# Sparkfun_MPU-9150_breakout.net
KiCad netlist of a schematic drawn in EAGLE
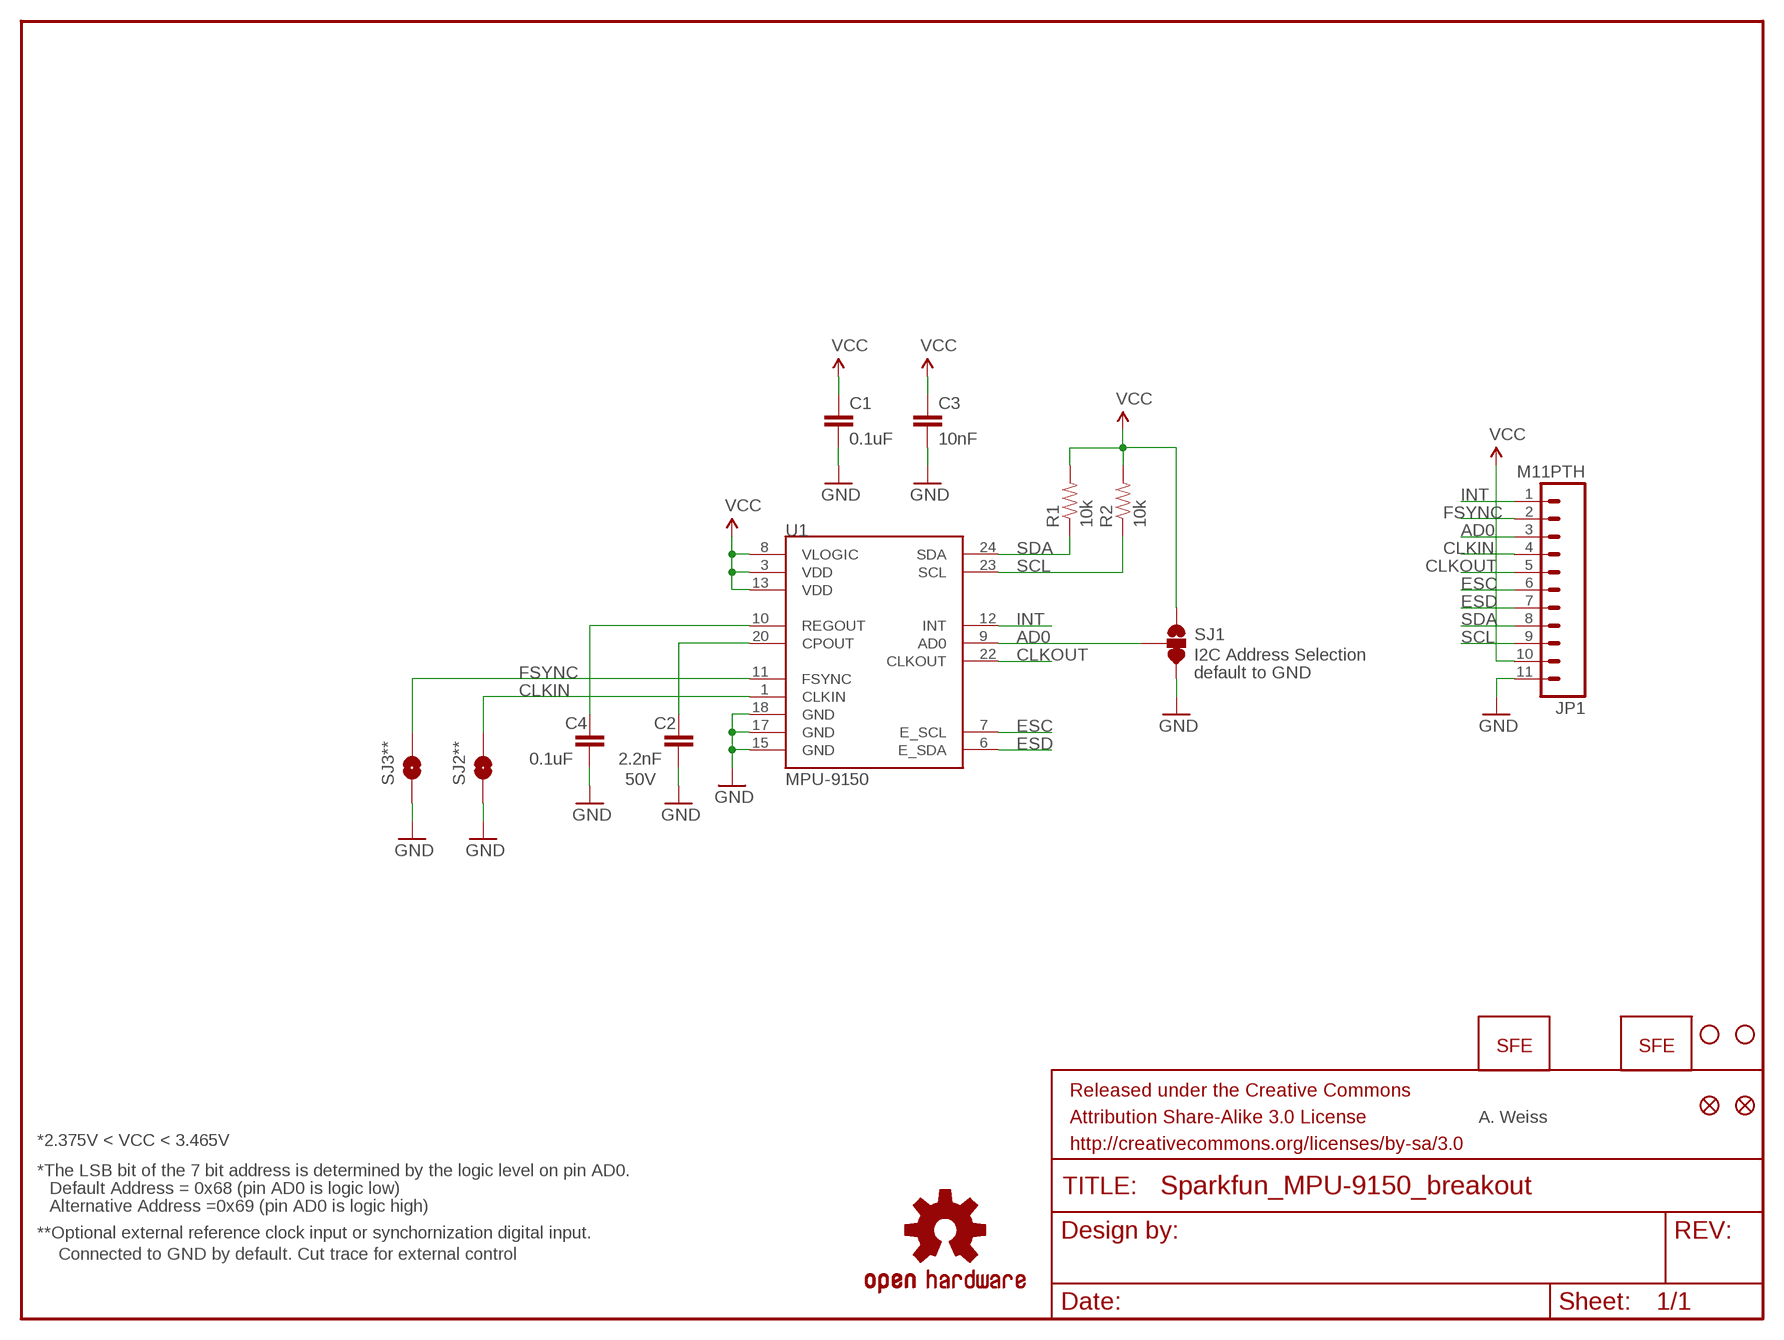
[diagram p0: schematic, sheet 1]

(export (version "E")
  (design (tool "Eeschema 10.0.6"))
  (components
    (comp (ref "C1")
      (value "0.1uF")
      (footprint "eagle-import:0402-CAP")
      (libsource (lib "eagle-import") (part "CAP0402-CAP"))
    )
    (comp (ref "C2")
      (value "2.2nF")
      (footprint "eagle-import:0402-CAP")
      (libsource (lib "eagle-import") (part "CAP0402-CAP"))
    )
    (comp (ref "C3")
      (value "10nF")
      (footprint "eagle-import:0402-CAP")
      (libsource (lib "eagle-import") (part "CAP0402-CAP"))
    )
    (comp (ref "C4")
      (value "0.1uF")
      (footprint "eagle-import:0402-CAP")
      (libsource (lib "eagle-import") (part "CAP0402-CAP"))
    )
    (comp (ref "JP1")
      (value "M11PTH")
      (footprint "eagle-import:1X11")
      (libsource (lib "eagle-import") (part "M11PTH"))
    )
    (comp (ref "JP2")
      (value "STAND-OFF")
      (footprint "eagle-import:STAND-OFF")
      (libsource (lib "eagle-import") (part "STAND-OFF"))
    )
    (comp (ref "JP3")
      (value "STAND-OFF")
      (footprint "eagle-import:STAND-OFF")
      (libsource (lib "eagle-import") (part "STAND-OFF"))
    )
    (comp (ref "JP4")
      (value "LOGO-SFENW2")
      (footprint "eagle-import:SFE-NEW-WEB")
      (libsource (lib "eagle-import") (part "LOGO-SFENW2"))
    )
    (comp (ref "JP6")
      (value "LOGO-SFESK")
      (footprint "eagle-import:SFE-LOGO-FLAME")
      (libsource (lib "eagle-import") (part "LOGO-SFESK"))
    )
    (comp (ref "JP7")
      (value "FIDUCIALUFIDUCIAL")
      (footprint "eagle-import:MICRO-FIDUCIAL")
      (libsource (lib "eagle-import") (part "FIDUCIALUFIDUCIAL"))
    )
    (comp (ref "JP8")
      (value "FIDUCIALUFIDUCIAL")
      (footprint "eagle-import:MICRO-FIDUCIAL")
      (libsource (lib "eagle-import") (part "FIDUCIALUFIDUCIAL"))
    )
    (comp (ref "R1")
      (value "10k")
      (footprint "eagle-import:0402-RES")
      (libsource (lib "eagle-import") (part "RESISTOR0402-RES"))
    )
    (comp (ref "R2")
      (value "10k")
      (footprint "eagle-import:0402-RES")
      (libsource (lib "eagle-import") (part "RESISTOR0402-RES"))
    )
    (comp (ref "SJ1")
      (value "SOLDERJUMPER_2WAYPASTE2&3")
      (footprint "eagle-import:SJ_3_PASTE2&3")
      (libsource (lib "eagle-import") (part "SOLDERJUMPER_2WAYPASTE2&3"))
    )
    (comp (ref "SJ2**")
      (value "SOLDERJUMPERTRACE")
      (footprint "eagle-import:SJ_2S-TRACE")
      (libsource (lib "eagle-import") (part "SOLDERJUMPERTRACE"))
    )
    (comp (ref "SJ3**")
      (value "SOLDERJUMPERTRACE")
      (footprint "eagle-import:SJ_2S-TRACE")
      (libsource (lib "eagle-import") (part "SOLDERJUMPERTRACE"))
    )
    (comp (ref "U$1")
      (value "OSHW-LOGOS")
      (footprint "eagle-import:OSHW-LOGO-S")
      (libsource (lib "eagle-import") (part "OSHW-LOGOS"))
    )
    (comp (ref "U1")
      (value "MPU-9150")
      (footprint "eagle-import:QFN-24-NP")
      (libsource (lib "eagle-import") (part "MPU-9150QFN-24-NP"))
    )
  )
  (nets
    (net (code "1") (name "/AD0") (class "Default")
      (node (ref "JP1") (pin "3") (pinfunction "3_3") (pintype "passive"))
      (node (ref "SJ1") (pin "2") (pinfunction "2_2") (pintype "passive"))
      (node (ref "U1") (pin "9") (pinfunction "AD0_9") (pintype "bidirectional"))
    )
    (net (code "2") (name "/CLKIN") (class "Default")
      (node (ref "JP1") (pin "4") (pinfunction "4_4") (pintype "passive"))
      (node (ref "SJ2**") (pin "2") (pinfunction "2_2") (pintype "passive"))
      (node (ref "U1") (pin "1") (pinfunction "CLKIN_1") (pintype "bidirectional"))
    )
    (net (code "3") (name "/CLKOUT") (class "Default")
      (node (ref "JP1") (pin "5") (pinfunction "5_5") (pintype "passive"))
      (node (ref "U1") (pin "22") (pinfunction "CLKOUT_22") (pintype "bidirectional"))
    )
    (net (code "4") (name "/ESC") (class "Default")
      (node (ref "JP1") (pin "6") (pinfunction "6_6") (pintype "passive"))
      (node (ref "U1") (pin "7") (pinfunction "E_SCL_7") (pintype "bidirectional"))
    )
    (net (code "5") (name "/ESD") (class "Default")
      (node (ref "JP1") (pin "7") (pinfunction "7_7") (pintype "passive"))
      (node (ref "U1") (pin "6") (pinfunction "E_SDA_6") (pintype "bidirectional"))
    )
    (net (code "6") (name "/FSYNC") (class "Default")
      (node (ref "JP1") (pin "2") (pinfunction "2_2") (pintype "passive"))
      (node (ref "SJ3**") (pin "2") (pinfunction "2_2") (pintype "passive"))
      (node (ref "U1") (pin "11") (pinfunction "FSYNC_11") (pintype "bidirectional"))
    )
    (net (code "7") (name "/INT") (class "Default")
      (node (ref "JP1") (pin "1") (pinfunction "1_1") (pintype "passive"))
      (node (ref "U1") (pin "12") (pinfunction "INT_12") (pintype "bidirectional"))
    )
    (net (code "8") (name "/SCL") (class "Default")
      (node (ref "JP1") (pin "8") (pinfunction "8_8") (pintype "passive"))
      (node (ref "R2") (pin "1") (pinfunction "1_1") (pintype "passive"))
      (node (ref "U1") (pin "23") (pinfunction "SCL_23") (pintype "bidirectional"))
    )
    (net (code "9") (name "/SDA") (class "Default")
      (node (ref "JP1") (pin "9") (pinfunction "9_9") (pintype "passive"))
      (node (ref "R1") (pin "1") (pinfunction "1_1") (pintype "passive"))
      (node (ref "U1") (pin "24") (pinfunction "SDA_24") (pintype "bidirectional"))
    )
    (net (code "10") (name "GND") (class "Default")
      (node (ref "C1") (pin "2") (pinfunction "2_2") (pintype "passive"))
      (node (ref "C2") (pin "2") (pinfunction "2_2") (pintype "passive"))
      (node (ref "C3") (pin "2") (pinfunction "2_2") (pintype "passive"))
      (node (ref "C4") (pin "2") (pinfunction "2_2") (pintype "passive"))
      (node (ref "JP1") (pin "11") (pinfunction "11_11") (pintype "passive"))
      (node (ref "SJ1") (pin "3") (pinfunction "3_3") (pintype "passive"))
      (node (ref "SJ2**") (pin "1") (pinfunction "1_1") (pintype "passive"))
      (node (ref "SJ3**") (pin "1") (pinfunction "1_1") (pintype "passive"))
      (node (ref "U1") (pin "15") (pinfunction "GND_15") (pintype "bidirectional"))
      (node (ref "U1") (pin "17") (pinfunction "GND_17") (pintype "bidirectional"))
      (node (ref "U1") (pin "18") (pinfunction "GND_18") (pintype "bidirectional"))
    )
    (net (code "11") (name "Net-(U1-CPOUT)") (class "Default")
      (node (ref "C2") (pin "1") (pinfunction "1_1") (pintype "passive"))
      (node (ref "U1") (pin "20") (pinfunction "CPOUT_20") (pintype "bidirectional"))
    )
    (net (code "12") (name "Net-(U1-REGOUT)") (class "Default")
      (node (ref "C4") (pin "1") (pinfunction "1_1") (pintype "passive"))
      (node (ref "U1") (pin "10") (pinfunction "REGOUT_10") (pintype "bidirectional"))
    )
    (net (code "13") (name "VCC") (class "Default")
      (node (ref "C1") (pin "1") (pinfunction "1_1") (pintype "passive"))
      (node (ref "C3") (pin "1") (pinfunction "1_1") (pintype "passive"))
      (node (ref "JP1") (pin "10") (pinfunction "10_10") (pintype "passive"))
      (node (ref "R1") (pin "2") (pinfunction "2_2") (pintype "passive"))
      (node (ref "R2") (pin "2") (pinfunction "2_2") (pintype "passive"))
      (node (ref "SJ1") (pin "1") (pinfunction "1_1") (pintype "passive"))
      (node (ref "U1") (pin "13") (pinfunction "VDD_13") (pintype "bidirectional"))
      (node (ref "U1") (pin "3") (pinfunction "VDD_3") (pintype "bidirectional"))
      (node (ref "U1") (pin "8") (pinfunction "VLOGIC_8") (pintype "bidirectional"))
    )
  )
)
